# MorseAttiny.net
KiCad netlist of a schematic drawn in EAGLE
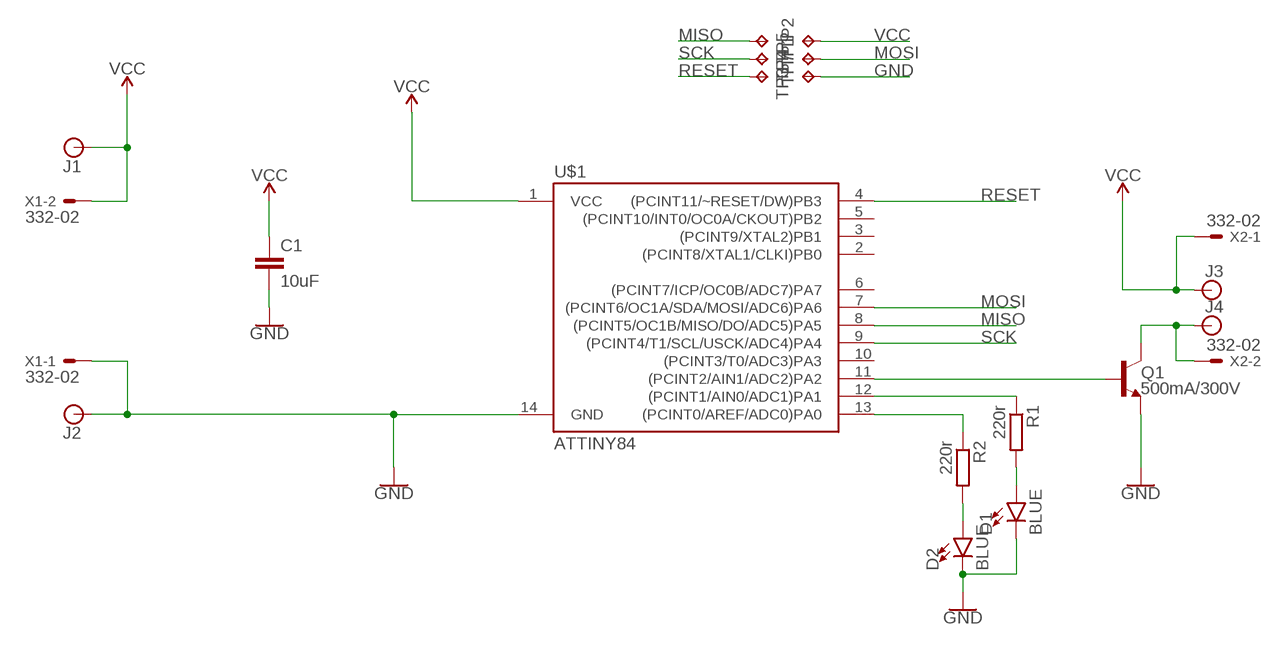
[diagram p0: schematic, sheet 1]

(export (version "E")
  (design (tool "Eeschema 10.0.6"))
  (components
    (comp (ref "C1")
      (value "10uF")
      (footprint "eagle-import:1210")
      (libsource (lib "eagle-import") (part "10UF-1210-50V-20%"))
    )
    (comp (ref "D1")
      (value "BLUE")
      (footprint "eagle-import:LED-1206")
      (libsource (lib "eagle-import") (part "LED-BLUE1206"))
    )
    (comp (ref "D2")
      (value "BLUE")
      (footprint "eagle-import:LED-1206")
      (libsource (lib "eagle-import") (part "LED-BLUE1206"))
    )
    (comp (ref "J1")
      (value "BANANA_CONN")
      (footprint "eagle-import:BANANA_CONN")
      (libsource (lib "eagle-import") (part "BANANA_CONN"))
    )
    (comp (ref "J2")
      (value "BANANA_CONN")
      (footprint "eagle-import:BANANA_CONN")
      (libsource (lib "eagle-import") (part "BANANA_CONN"))
    )
    (comp (ref "J3")
      (value "BANANA_CONN")
      (footprint "eagle-import:BANANA_CONN")
      (libsource (lib "eagle-import") (part "BANANA_CONN"))
    )
    (comp (ref "J4")
      (value "BANANA_CONN")
      (footprint "eagle-import:BANANA_CONN")
      (libsource (lib "eagle-import") (part "BANANA_CONN"))
    )
    (comp (ref "Q1")
      (value "500mA/300V")
      (footprint "eagle-import:SOT23-3")
      (libsource (lib "eagle-import") (part "TRANS_NPN-MMBTA42"))
    )
    (comp (ref "R1")
      (value "220r")
      (footprint "eagle-import:M0805")
      (libsource (lib "eagle-import") (part "R-EU_M0805"))
    )
    (comp (ref "R2")
      (value "220r")
      (footprint "eagle-import:M0805")
      (libsource (lib "eagle-import") (part "R-EU_M0805"))
    )
    (comp (ref "TP1")
      (value "TPTP18R")
      (footprint "eagle-import:TP18R")
      (libsource (lib "eagle-import") (part "TPTP18R"))
    )
    (comp (ref "TP2")
      (value "TPTP18R")
      (footprint "eagle-import:TP18R")
      (libsource (lib "eagle-import") (part "TPTP18R"))
    )
    (comp (ref "TP3")
      (value "TPTP18R")
      (footprint "eagle-import:TP18R")
      (libsource (lib "eagle-import") (part "TPTP18R"))
    )
    (comp (ref "TP4")
      (value "TPTP18R")
      (footprint "eagle-import:TP18R")
      (libsource (lib "eagle-import") (part "TPTP18R"))
    )
    (comp (ref "TP5")
      (value "TPTP18R")
      (footprint "eagle-import:TP18R")
      (libsource (lib "eagle-import") (part "TPTP18R"))
    )
    (comp (ref "TP7")
      (value "TPTP18R")
      (footprint "eagle-import:TP18R")
      (libsource (lib "eagle-import") (part "TPTP18R"))
    )
    (comp (ref "U$1")
      (value "ATTINY84")
      (footprint "eagle-import:SO14")
      (libsource (lib "eagle-import") (part "ATTINY84"))
    )
    (comp (ref "X1")
      (value "332-02")
      (footprint "eagle-import:332-02")
      (libsource (lib "eagle-import") (part "332-02"))
    )
    (comp (ref "X2")
      (value "332-02")
      (footprint "eagle-import:332-02")
      (libsource (lib "eagle-import") (part "332-02"))
    )
  )
  (nets
    (net (code "1") (name "/MISO") (class "Default")
      (node (ref "TP5") (pin "TP") (pinfunction "TP_TP") (pintype "input"))
      (node (ref "U$1") (pin "8") (pinfunction "(PCINT5/OC1B/MISO/DO/ADC5)PA5_8") (pintype "bidirectional"))
    )
    (net (code "2") (name "/MOSI") (class "Default")
      (node (ref "TP1") (pin "TP") (pinfunction "TP_TP") (pintype "input"))
      (node (ref "U$1") (pin "7") (pinfunction "(PCINT6/OC1A/SDA/MOSI/ADC6)PA6_7") (pintype "bidirectional"))
    )
    (net (code "3") (name "/RESET") (class "Default")
      (node (ref "TP3") (pin "TP") (pinfunction "TP_TP") (pintype "input"))
      (node (ref "U$1") (pin "4") (pinfunction "(PCINT11/~{RESET/DW})PB3_4") (pintype "bidirectional"))
    )
    (net (code "4") (name "/SCK") (class "Default")
      (node (ref "TP4") (pin "TP") (pinfunction "TP_TP") (pintype "input"))
      (node (ref "U$1") (pin "9") (pinfunction "(PCINT4/T1/SCL/USCK/ADC4)PA4_9") (pintype "bidirectional"))
    )
    (net (code "5") (name "GND") (class "Default")
      (node (ref "C1") (pin "2") (pinfunction "2_2") (pintype "passive"))
      (node (ref "D1") (pin "C") (pinfunction "C_C") (pintype "passive"))
      (node (ref "D2") (pin "C") (pinfunction "C_C") (pintype "passive"))
      (node (ref "J2") (pin "P$1") (pinfunction "1_P$1") (pintype "passive"))
      (node (ref "Q1") (pin "2") (pinfunction "E_2") (pintype "passive"))
      (node (ref "TP7") (pin "TP") (pinfunction "TP_TP") (pintype "input"))
      (node (ref "U$1") (pin "14") (pinfunction "GND_14") (pintype "bidirectional"))
      (node (ref "X1") (pin "1") (pinfunction "S_1") (pintype "passive"))
    )
    (net (code "6") (name "Net-(D1-PadA)") (class "Default")
      (node (ref "D1") (pin "A") (pinfunction "A_A") (pintype "passive"))
      (node (ref "R1") (pin "2") (pinfunction "2_2") (pintype "passive"))
    )
    (net (code "7") (name "Net-(D2-PadA)") (class "Default")
      (node (ref "D2") (pin "A") (pinfunction "A_A") (pintype "passive"))
      (node (ref "R2") (pin "2") (pinfunction "2_2") (pintype "passive"))
    )
    (net (code "8") (name "Net-(J4-1)") (class "Default")
      (node (ref "J4") (pin "P$1") (pinfunction "1_P$1") (pintype "passive"))
      (node (ref "Q1") (pin "3") (pinfunction "C_3") (pintype "passive"))
      (node (ref "X2") (pin "2") (pinfunction "S_2") (pintype "passive"))
    )
    (net (code "9") (name "Net-(Q1-B)") (class "Default")
      (node (ref "Q1") (pin "1") (pinfunction "B_1") (pintype "passive"))
      (node (ref "U$1") (pin "11") (pinfunction "(PCINT2/AIN1/ADC2)PA2_11") (pintype "bidirectional"))
    )
    (net (code "10") (name "Net-(U$1-(PCINT0{slash}AREF{slash}ADC0)PA0)") (class "Default")
      (node (ref "R2") (pin "1") (pinfunction "1_1") (pintype "passive"))
      (node (ref "U$1") (pin "13") (pinfunction "(PCINT0/AREF/ADC0)PA0_13") (pintype "bidirectional"))
    )
    (net (code "11") (name "Net-(U$1-(PCINT1{slash}AIN0{slash}ADC1)PA1)") (class "Default")
      (node (ref "R1") (pin "1") (pinfunction "1_1") (pintype "passive"))
      (node (ref "U$1") (pin "12") (pinfunction "(PCINT1/AIN0/ADC1)PA1_12") (pintype "bidirectional"))
    )
    (net (code "12") (name "VCC") (class "Default")
      (node (ref "C1") (pin "1") (pinfunction "1_1") (pintype "passive"))
      (node (ref "J1") (pin "P$1") (pinfunction "1_P$1") (pintype "passive"))
      (node (ref "J3") (pin "P$1") (pinfunction "1_P$1") (pintype "passive"))
      (node (ref "TP2") (pin "TP") (pinfunction "TP_TP") (pintype "input"))
      (node (ref "U$1") (pin "1") (pinfunction "VCC_1") (pintype "bidirectional"))
      (node (ref "X1") (pin "2") (pinfunction "S_2") (pintype "passive"))
      (node (ref "X2") (pin "1") (pinfunction "S_1") (pintype "passive"))
    )
    (net (code "13") (name "unconnected-(U$1-(PCINT3{slash}T0{slash}ADC3)PA3-Pad10)") (class "Default")
      (node (ref "U$1") (pin "10") (pinfunction "(PCINT3/T0/ADC3)PA3_10") (pintype "bidirectional"))
    )
    (net (code "14") (name "unconnected-(U$1-(PCINT7{slash}ICP{slash}OC0B{slash}ADC7)PA7-Pad6)") (class "Default")
      (node (ref "U$1") (pin "6") (pinfunction "(PCINT7/ICP/OC0B/ADC7)PA7_6") (pintype "bidirectional"))
    )
    (net (code "15") (name "unconnected-(U$1-(PCINT8{slash}XTAL1{slash}CLKI)PB0-Pad2)") (class "Default")
      (node (ref "U$1") (pin "2") (pinfunction "(PCINT8/XTAL1/CLKI)PB0_2") (pintype "bidirectional"))
    )
    (net (code "16") (name "unconnected-(U$1-(PCINT9{slash}XTAL2)PB1-Pad3)") (class "Default")
      (node (ref "U$1") (pin "3") (pinfunction "(PCINT9/XTAL2)PB1_3") (pintype "bidirectional"))
    )
    (net (code "17") (name "unconnected-(U$1-(PCINT10{slash}INT0{slash}OC0A{slash}CKOUT)PB2-Pad5)") (class "Default")
      (node (ref "U$1") (pin "5") (pinfunction "(PCINT10/INT0/OC0A/CKOUT)PB2_5") (pintype "bidirectional"))
    )
  )
)
